# Arduino_FPGA_Design.net
KiCad netlist of a schematic drawn in Altium Designer
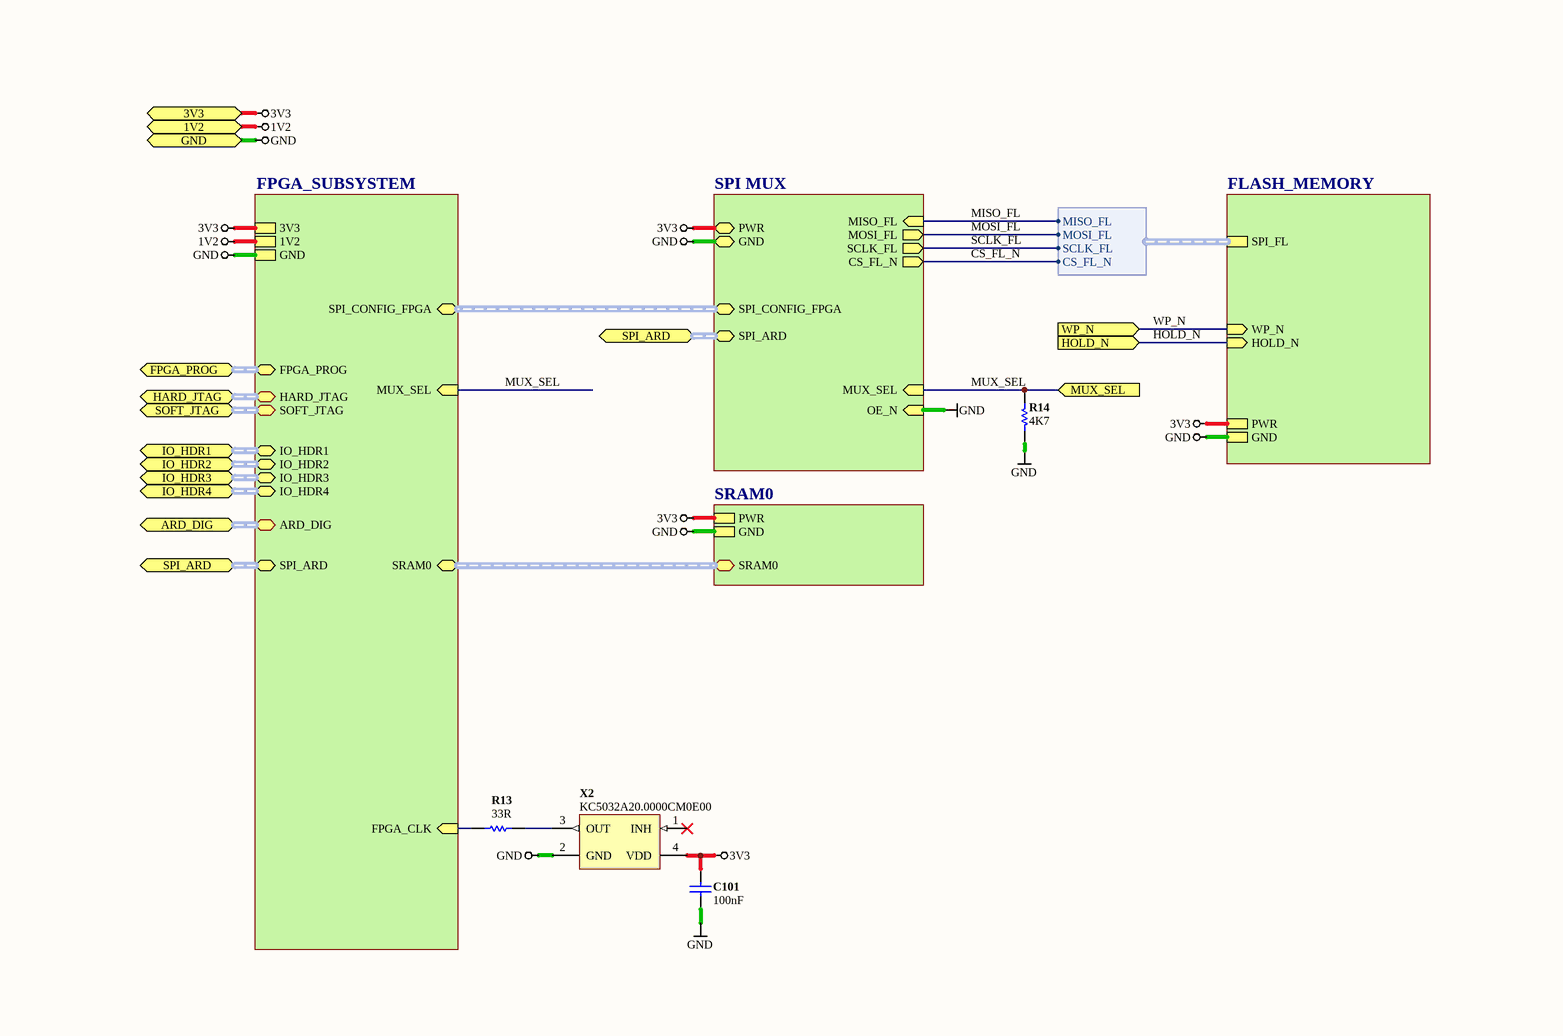
[diagram p0: Arduino FPGA Design.SchDoc]

(export (version "E")
  (design (tool "Eeschema 10.0.6"))
  (components
    (comp (ref "C101")
      (value "100nF")
      (footprint "CAPC0402(1005)60_L")
      (fields (field (name "TOLERANCE") "±10%") (field (name "Comment") "CAP 100nF 16V 0402(1005)"))
      (libsource (lib "Component_Database") (part "CAP_NP"))
    )
    (comp (ref "R13")
      (value "33R")
      (footprint "RESC0402(1005)40_L")
      (fields (field (name "POWER") "1/16 W") (field (name "Comment") "33R 1 0402"))
      (libsource (lib "Component_Database") (part "RES"))
    )
    (comp (ref "R14")
      (value "4K7")
      (footprint "RESC0402(1005)40_L")
      (fields (field (name "POWER") "1/16 W") (field (name "Comment") "4K7 1 0402"))
      (libsource (lib "Component_Database") (part "RES"))
    )
    (comp (ref "X2")
      (value "KC5032A20.0000CM0E00")
      (footprint "HOSC-L500HW320H105-4_2")
      (fields (field (name "PARTNUMBER") "HCX-C2-20M"))
      (libsource (lib "Component_Database") (part "OSC-4"))
    )
  )
  (nets
    (net (code "13") (name "/FPGA_CLK") (class "Default")
      (node (ref "R13") (pin "1") (pinfunction "1_1") (pintype "passive"))
    )
    (net (code "23") (name "/MUX_SEL") (class "Default")
      (node (ref "R14") (pin "2") (pinfunction "2_2") (pintype "passive"))
    )
    (net (code "32") (name "3V3") (class "Default")
      (node (ref "C101") (pin "1") (pinfunction "1_1") (pintype "passive"))
      (node (ref "X2") (pin "4") (pinfunction "VDD_4") (pintype "power_in"))
    )
    (net (code "33") (name "GND") (class "Default")
      (node (ref "C101") (pin "2") (pinfunction "2_2") (pintype "passive"))
      (node (ref "R14") (pin "1") (pinfunction "1_1") (pintype "passive"))
      (node (ref "X2") (pin "2") (pinfunction "GND_2") (pintype "power_in"))
    )
    (net (code "34") (name "Net-(X2-OUT)") (class "Default")
      (node (ref "R13") (pin "2") (pinfunction "2_2") (pintype "passive"))
      (node (ref "X2") (pin "3") (pinfunction "OUT_3") (pintype "output"))
    )
    (net (code "35") (name "unconnected-(X2-INH-Pad1)") (class "Default")
      (node (ref "X2") (pin "1") (pinfunction "INH_1") (pintype "input+no_connect"))
    )
  )
)
